# esp32_c6_a1_SoC.net
KiCad netlist of a schematic drawn in Altium Designer
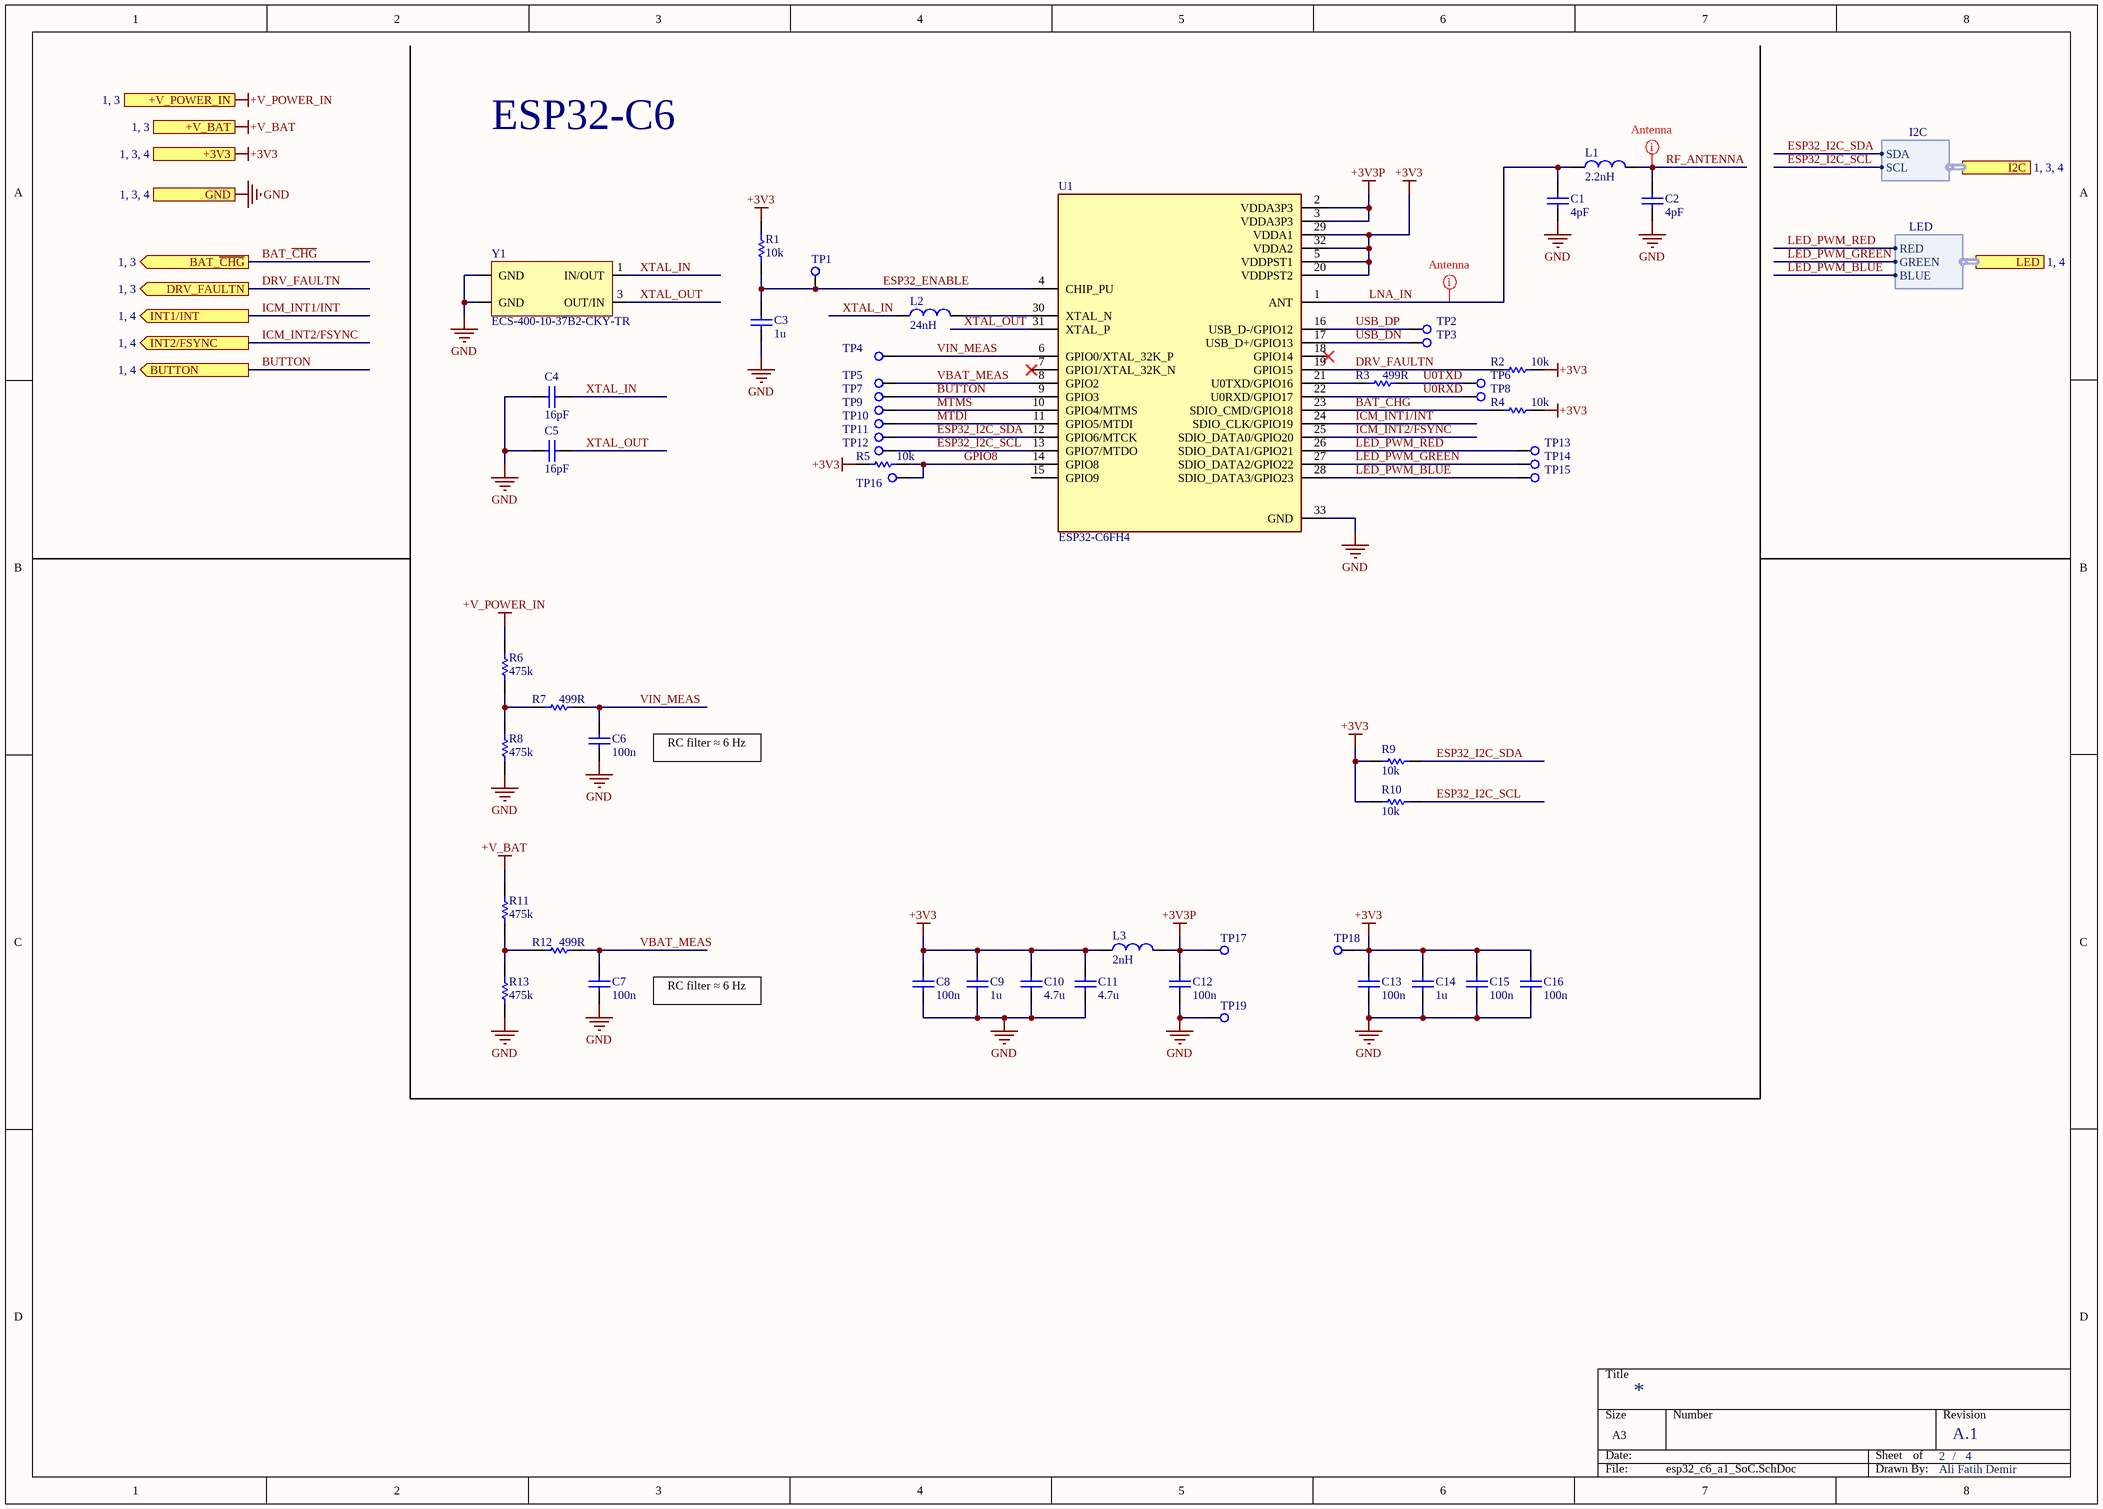
[diagram p0: esp32_c6_a1_SoC.SchDoc]

(export (version "E")
  (design (tool "Eeschema 10.0.6"))
  (components
    (comp (ref "C1")
      (value "4pF")
      (footprint "C_0201")
      (description "SMD 0201 Ceramic Chip Capacitor")
      (fields (field (name "MANUFACTURER") "Murata") (field (name "PART NUMBER") "?"))
      (libsource (lib "afd_lib") (part "C_0201"))
    )
    (comp (ref "C2")
      (value "4pF")
      (footprint "C_0201")
      (description "SMD 0201 Ceramic Chip Capacitor")
      (fields (field (name "MANUFACTURER") "Murata") (field (name "PART NUMBER") "?"))
      (libsource (lib "afd_lib") (part "C_0201"))
    )
    (comp (ref "C3")
      (value "1u")
      (footprint "C_0603")
      (description "SMD 0603 Ceramic Chip Capacitor")
      (fields (field (name "MANUFACTURER") "Samsung") (field (name "PART NUMBER") "?"))
      (libsource (lib "afd_lib") (part "C_0603"))
    )
    (comp (ref "C4")
      (value "16pF")
      (footprint "C_0402")
      (description "SMD 0402 Ceramic Chip Capacitor")
      (fields (field (name "MANUFACTURER") "Murata") (field (name "PART NUMBER") "?"))
      (libsource (lib "afd_lib") (part "C_0402"))
    )
    (comp (ref "C5")
      (value "16pF")
      (footprint "C_0402")
      (description "SMD 0402 Ceramic Chip Capacitor")
      (fields (field (name "MANUFACTURER") "Murata") (field (name "PART NUMBER") "?"))
      (libsource (lib "afd_lib") (part "C_0402"))
    )
    (comp (ref "C6")
      (value "100n")
      (footprint "C_0402")
      (description "SMD 0402 Ceramic Chip Capacitor")
      (fields (field (name "MANUFACTURER") "Samsung") (field (name "PART NUMBER") "?"))
      (libsource (lib "afd_lib") (part "C_0402"))
    )
    (comp (ref "C7")
      (value "100n")
      (footprint "C_0402")
      (description "SMD 0402 Ceramic Chip Capacitor")
      (fields (field (name "MANUFACTURER") "Samsung") (field (name "PART NUMBER") "?"))
      (libsource (lib "afd_lib") (part "C_0402"))
    )
    (comp (ref "C8")
      (value "100n")
      (footprint "C_0402")
      (description "SMD 0402 Ceramic Chip Capacitor")
      (fields (field (name "MANUFACTURER") "Samsung") (field (name "PART NUMBER") "?"))
      (libsource (lib "afd_lib") (part "C_0402"))
    )
    (comp (ref "C9")
      (value "1u")
      (footprint "C_0603")
      (description "SMD 0603 Ceramic Chip Capacitor")
      (fields (field (name "MANUFACTURER") "Samsung") (field (name "PART NUMBER") "?"))
      (libsource (lib "afd_lib") (part "C_0603"))
    )
    (comp (ref "C10")
      (value "4.7u")
      (footprint "C_0603")
      (description "SMD 0603 Ceramic Chip Capacitor")
      (fields (field (name "MANUFACTURER") "Samsung") (field (name "PART NUMBER") "?"))
      (libsource (lib "afd_lib") (part "C_0603"))
    )
    (comp (ref "C11")
      (value "4.7u")
      (footprint "C_0603")
      (description "SMD 0603 Ceramic Chip Capacitor")
      (fields (field (name "MANUFACTURER") "Samsung") (field (name "PART NUMBER") "?"))
      (libsource (lib "afd_lib") (part "C_0603"))
    )
    (comp (ref "C12")
      (value "100n")
      (footprint "C_0402")
      (description "SMD 0402 Ceramic Chip Capacitor")
      (fields (field (name "MANUFACTURER") "Samsung") (field (name "PART NUMBER") "?"))
      (libsource (lib "afd_lib") (part "C_0402"))
    )
    (comp (ref "C13")
      (value "100n")
      (footprint "C_0402")
      (description "SMD 0402 Ceramic Chip Capacitor")
      (fields (field (name "MANUFACTURER") "Samsung") (field (name "PART NUMBER") "?"))
      (libsource (lib "afd_lib") (part "C_0402"))
    )
    (comp (ref "C14")
      (value "1u")
      (footprint "C_0603")
      (description "SMD 0603 Ceramic Chip Capacitor")
      (fields (field (name "MANUFACTURER") "Samsung") (field (name "PART NUMBER") "?"))
      (libsource (lib "afd_lib") (part "C_0603"))
    )
    (comp (ref "C15")
      (value "100n")
      (footprint "C_0402")
      (description "SMD 0402 Ceramic Chip Capacitor")
      (fields (field (name "MANUFACTURER") "Samsung") (field (name "PART NUMBER") "?"))
      (libsource (lib "afd_lib") (part "C_0402"))
    )
    (comp (ref "C16")
      (value "100n")
      (footprint "C_0402")
      (description "SMD 0402 Ceramic Chip Capacitor")
      (fields (field (name "MANUFACTURER") "Samsung") (field (name "PART NUMBER") "?"))
      (libsource (lib "afd_lib") (part "C_0402"))
    )
    (comp (ref "L1")
      (value "2.2nH")
      (footprint "L_0201")
      (description "SMD 0201 Inductor")
      (fields (field (name "MANUFACTURER") "Murata") (field (name "PART NUMBER") "?"))
      (libsource (lib "afd_lib") (part "L_0201"))
    )
    (comp (ref "L2")
      (value "24nH")
      (footprint "L_0201")
      (description "SMD 0201 Inductor")
      (fields (field (name "MANUFACTURER") "Murata") (field (name "PART NUMBER") "?"))
      (libsource (lib "afd_lib") (part "L_0201"))
    )
    (comp (ref "L3")
      (value "2nH")
      (footprint "L_0402")
      (description "SMD 0402 Inductor")
      (fields (field (name "MANUFACTURER") "Murata") (field (name "PART NUMBER") "?"))
      (libsource (lib "afd_lib") (part "L_0402"))
    )
    (comp (ref "R1")
      (value "10k")
      (footprint "R_0402")
      (description "SMD 0402 Rectangular Thick Film Chip Resistor")
      (fields (field (name "MANUFACTURER") "Yageo") (field (name "PART NUMBER") "?"))
      (libsource (lib "afd_lib") (part "R_0402"))
    )
    (comp (ref "R2")
      (value "10k")
      (footprint "R_0402")
      (description "SMD 0402 Rectangular Thick Film Chip Resistor")
      (fields (field (name "MANUFACTURER") "Yageo") (field (name "PART NUMBER") "?"))
      (libsource (lib "afd_lib") (part "R_0402"))
    )
    (comp (ref "R3")
      (value "499R")
      (footprint "R_0402")
      (description "SMD 0402 Rectangular Thick Film Chip Resistor")
      (fields (field (name "MANUFACTURER") "Yageo") (field (name "PART NUMBER") "?"))
      (libsource (lib "afd_lib") (part "R_0402"))
    )
    (comp (ref "R4")
      (value "10k")
      (footprint "R_0402")
      (description "SMD 0402 Rectangular Thick Film Chip Resistor")
      (fields (field (name "MANUFACTURER") "Yageo") (field (name "PART NUMBER") "?"))
      (libsource (lib "afd_lib") (part "R_0402"))
    )
    (comp (ref "R5")
      (value "10k")
      (footprint "R_0402")
      (description "SMD 0402 Rectangular Thick Film Chip Resistor")
      (fields (field (name "MANUFACTURER") "Yageo") (field (name "PART NUMBER") "?"))
      (libsource (lib "afd_lib") (part "R_0402"))
    )
    (comp (ref "R6")
      (value "475k")
      (footprint "R_0402")
      (description "SMD 0402 Rectangular Thick Film Chip Resistor")
      (fields (field (name "MANUFACTURER") "Yageo") (field (name "PART NUMBER") "?"))
      (libsource (lib "afd_lib") (part "R_0402"))
    )
    (comp (ref "R7")
      (value "499R")
      (footprint "R_0402")
      (description "SMD 0402 Rectangular Thick Film Chip Resistor")
      (fields (field (name "MANUFACTURER") "Yageo") (field (name "PART NUMBER") "?"))
      (libsource (lib "afd_lib") (part "R_0402"))
    )
    (comp (ref "R8")
      (value "475k")
      (footprint "R_0402")
      (description "SMD 0402 Rectangular Thick Film Chip Resistor")
      (fields (field (name "MANUFACTURER") "Yageo") (field (name "PART NUMBER") "?"))
      (libsource (lib "afd_lib") (part "R_0402"))
    )
    (comp (ref "R9")
      (value "10k")
      (footprint "R_0402")
      (description "SMD 0402 Rectangular Thick Film Chip Resistor")
      (fields (field (name "MANUFACTURER") "Yageo") (field (name "PART NUMBER") "?"))
      (libsource (lib "afd_lib") (part "R_0402"))
    )
    (comp (ref "R10")
      (value "10k")
      (footprint "R_0402")
      (description "SMD 0402 Rectangular Thick Film Chip Resistor")
      (fields (field (name "MANUFACTURER") "Yageo") (field (name "PART NUMBER") "?"))
      (libsource (lib "afd_lib") (part "R_0402"))
    )
    (comp (ref "R11")
      (value "475k")
      (footprint "R_0402")
      (description "SMD 0402 Rectangular Thick Film Chip Resistor")
      (fields (field (name "MANUFACTURER") "Yageo") (field (name "PART NUMBER") "?"))
      (libsource (lib "afd_lib") (part "R_0402"))
    )
    (comp (ref "R12")
      (value "499R")
      (footprint "R_0402")
      (description "SMD 0402 Rectangular Thick Film Chip Resistor")
      (fields (field (name "MANUFACTURER") "Yageo") (field (name "PART NUMBER") "?"))
      (libsource (lib "afd_lib") (part "R_0402"))
    )
    (comp (ref "R13")
      (value "475k")
      (footprint "R_0402")
      (description "SMD 0402 Rectangular Thick Film Chip Resistor")
      (fields (field (name "MANUFACTURER") "Yageo") (field (name "PART NUMBER") "?"))
      (libsource (lib "afd_lib") (part "R_0402"))
    )
    (comp (ref "TP1")
      (value "TP")
      (footprint "tp_round_80")
      (description "Test Point")
      (libsource (lib "afd_lib") (part "TP"))
    )
    (comp (ref "TP2")
      (value "TP")
      (footprint "tp_round_80")
      (description "Test Point")
      (libsource (lib "afd_lib") (part "TP"))
    )
    (comp (ref "TP3")
      (value "TP")
      (footprint "tp_round_80")
      (description "Test Point")
      (libsource (lib "afd_lib") (part "TP"))
    )
    (comp (ref "TP4")
      (value "TP")
      (footprint "tp_round_80")
      (description "Test Point")
      (libsource (lib "afd_lib") (part "TP"))
    )
    (comp (ref "TP5")
      (value "TP")
      (footprint "tp_round_80")
      (description "Test Point")
      (libsource (lib "afd_lib") (part "TP"))
    )
    (comp (ref "TP6")
      (value "TP")
      (footprint "tp_round_80")
      (description "Test Point")
      (libsource (lib "afd_lib") (part "TP"))
    )
    (comp (ref "TP7")
      (value "TP")
      (footprint "tp_round_80")
      (description "Test Point")
      (libsource (lib "afd_lib") (part "TP"))
    )
    (comp (ref "TP8")
      (value "TP")
      (footprint "tp_round_80")
      (description "Test Point")
      (libsource (lib "afd_lib") (part "TP"))
    )
    (comp (ref "TP9")
      (value "TP")
      (footprint "tp_round_80")
      (description "Test Point")
      (libsource (lib "afd_lib") (part "TP"))
    )
    (comp (ref "TP10")
      (value "TP")
      (footprint "tp_round_80")
      (description "Test Point")
      (libsource (lib "afd_lib") (part "TP"))
    )
    (comp (ref "TP11")
      (value "TP")
      (footprint "tp_round_80")
      (description "Test Point")
      (libsource (lib "afd_lib") (part "TP"))
    )
    (comp (ref "TP12")
      (value "TP")
      (footprint "tp_round_80")
      (description "Test Point")
      (libsource (lib "afd_lib") (part "TP"))
    )
    (comp (ref "TP13")
      (value "TP")
      (footprint "tp_round_80")
      (description "Test Point")
      (libsource (lib "afd_lib") (part "TP"))
    )
    (comp (ref "TP14")
      (value "TP")
      (footprint "tp_round_80")
      (description "Test Point")
      (libsource (lib "afd_lib") (part "TP"))
    )
    (comp (ref "TP15")
      (value "TP")
      (footprint "tp_round_80")
      (description "Test Point")
      (libsource (lib "afd_lib") (part "TP"))
    )
    (comp (ref "TP16")
      (value "TP")
      (footprint "tp_round_80")
      (description "Test Point")
      (libsource (lib "afd_lib") (part "TP"))
    )
    (comp (ref "TP17")
      (value "TP")
      (footprint "tp_round_80")
      (description "Test Point")
      (libsource (lib "afd_lib") (part "TP"))
    )
    (comp (ref "TP18")
      (value "TP")
      (footprint "tp_round_80")
      (description "Test Point")
      (libsource (lib "afd_lib") (part "TP"))
    )
    (comp (ref "TP19")
      (value "TP")
      (footprint "tp_round_80")
      (description "Test Point")
      (libsource (lib "afd_lib") (part "TP"))
    )
    (comp (ref "U1")
      (value "ESP32-C6FH4")
      (footprint "QFN50P500X500X90-33N")
      (fields (field (name "MANUFACTURER") "Espressif Systems"))
      (libsource (lib "afd_lib") (part "ESP32-C6FH4"))
    )
    (comp (ref "Y1")
      (value "ECS-400-10-37B2-CKY-TR")
      (footprint "XTAL_ECS-400-10-37B2-CKY-TR")
      (description "40 MHz Â±10ppm Crystal 10pF 40 Ohms 4-SMD, No Lead")
      (fields
        (field (name "DIGI-KEY_PART_NUMBER") "50-ECS-400-10-37B2-CKY-TR-ND")
        (field (name "MANUFACTURER") "ECS Inc.")
      )
      (libsource (lib "afd_lib") (part "ECS-400-10-37B2-CKY-TR"))
    )
  )
  (nets
    (net (code "3") (name "+3V3") (class "Default")
      (node (ref "C10") (pin "2") (pinfunction "2_2") (pintype "passive"))
      (node (ref "C11") (pin "2") (pinfunction "2_2") (pintype "passive"))
      (node (ref "C13") (pin "2") (pinfunction "2_2") (pintype "passive"))
      (node (ref "C14") (pin "2") (pinfunction "2_2") (pintype "passive"))
      (node (ref "C15") (pin "2") (pinfunction "2_2") (pintype "passive"))
      (node (ref "C16") (pin "2") (pinfunction "2_2") (pintype "passive"))
      (node (ref "C8") (pin "2") (pinfunction "2_2") (pintype "passive"))
      (node (ref "C9") (pin "2") (pinfunction "2_2") (pintype "passive"))
      (node (ref "L3") (pin "1") (pinfunction "1_1") (pintype "passive"))
      (node (ref "R1") (pin "2") (pinfunction "2_2") (pintype "passive"))
      (node (ref "R10") (pin "2") (pinfunction "2_2") (pintype "passive"))
      (node (ref "R2") (pin "2") (pinfunction "2_2") (pintype "passive"))
      (node (ref "R4") (pin "2") (pinfunction "2_2") (pintype "passive"))
      (node (ref "R5") (pin "1") (pinfunction "1_1") (pintype "passive"))
      (node (ref "R9") (pin "2") (pinfunction "2_2") (pintype "passive"))
      (node (ref "TP18") (pin "1") (pinfunction "1_1") (pintype "passive"))
      (node (ref "U1") (pin "20") (pinfunction "VDDPST2_20") (pintype "passive"))
      (node (ref "U1") (pin "29") (pinfunction "VDDA1_29") (pintype "passive"))
      (node (ref "U1") (pin "32") (pinfunction "VDDA2_32") (pintype "passive"))
      (node (ref "U1") (pin "5") (pinfunction "VDDPST1_5") (pintype "passive"))
    )
    (net (code "4") (name "+3V3P") (class "Default")
      (node (ref "C12") (pin "2") (pinfunction "2_2") (pintype "passive"))
      (node (ref "L3") (pin "2") (pinfunction "2_2") (pintype "passive"))
      (node (ref "TP17") (pin "1") (pinfunction "1_1") (pintype "passive"))
      (node (ref "U1") (pin "2") (pinfunction "VDDA3P3_2") (pintype "passive"))
      (node (ref "U1") (pin "3") (pinfunction "VDDA3P3_3") (pintype "passive"))
    )
    (net (code "5") (name "+V_BAT") (class "Default")
      (node (ref "R11") (pin "2") (pinfunction "2_2") (pintype "passive"))
    )
    (net (code "6") (name "+V_POWER_IN") (class "Default")
      (node (ref "R6") (pin "2") (pinfunction "2_2") (pintype "passive"))
    )
    (net (code "7") (name "/BAT_~{CHG}") (class "Default")
      (node (ref "R4") (pin "1") (pinfunction "1_1") (pintype "passive"))
      (node (ref "U1") (pin "23") (pinfunction "SDIO_CMD/GPIO18_23") (pintype "passive"))
    )
    (net (code "8") (name "/BUTTON") (class "Default")
      (node (ref "TP7") (pin "1") (pinfunction "1_1") (pintype "passive"))
      (node (ref "U1") (pin "9") (pinfunction "GPIO3_9") (pintype "passive"))
    )
    (net (code "9") (name "/DRV_FAULTN") (class "Default")
      (node (ref "R2") (pin "1") (pinfunction "1_1") (pintype "passive"))
      (node (ref "U1") (pin "19") (pinfunction "GPIO15_19") (pintype "passive"))
    )
    (net (code "10") (name "/ESP32_ENABLE") (class "Default")
      (node (ref "C3") (pin "2") (pinfunction "2_2") (pintype "passive"))
      (node (ref "R1") (pin "1") (pinfunction "1_1") (pintype "passive"))
      (node (ref "TP1") (pin "1") (pinfunction "1_1") (pintype "passive"))
      (node (ref "U1") (pin "4") (pinfunction "CHIP_PU_4") (pintype "passive"))
    )
    (net (code "11") (name "/ESP32_I2C_SCL") (class "Default")
      (node (ref "R10") (pin "1") (pinfunction "1_1") (pintype "passive"))
      (node (ref "TP12") (pin "1") (pinfunction "1_1") (pintype "passive"))
      (node (ref "U1") (pin "13") (pinfunction "GPIO7/MTDO_13") (pintype "passive"))
    )
    (net (code "12") (name "/ESP32_I2C_SDA") (class "Default")
      (node (ref "R9") (pin "1") (pinfunction "1_1") (pintype "passive"))
      (node (ref "TP11") (pin "1") (pinfunction "1_1") (pintype "passive"))
      (node (ref "U1") (pin "12") (pinfunction "GPIO6/MTCK_12") (pintype "passive"))
    )
    (net (code "13") (name "/GPIO8") (class "Default")
      (node (ref "R5") (pin "2") (pinfunction "2_2") (pintype "passive"))
      (node (ref "TP16") (pin "1") (pinfunction "1_1") (pintype "passive"))
      (node (ref "U1") (pin "14") (pinfunction "GPIO8_14") (pintype "passive"))
    )
    (net (code "14") (name "/ICM_INT1{slash}INT") (class "Default")
      (node (ref "U1") (pin "24") (pinfunction "SDIO_CLK/GPIO19_24") (pintype "passive"))
    )
    (net (code "15") (name "/ICM_INT2{slash}FSYNC") (class "Default")
      (node (ref "U1") (pin "25") (pinfunction "SDIO_DATA0/GPIO20_25") (pintype "passive"))
    )
    (net (code "16") (name "/LED_PWM_BLUE") (class "Default")
      (node (ref "TP15") (pin "1") (pinfunction "1_1") (pintype "passive"))
      (node (ref "U1") (pin "28") (pinfunction "SDIO_DATA3/GPIO23_28") (pintype "passive"))
    )
    (net (code "17") (name "/LED_PWM_GREEN") (class "Default")
      (node (ref "TP14") (pin "1") (pinfunction "1_1") (pintype "passive"))
      (node (ref "U1") (pin "27") (pinfunction "SDIO_DATA2/GPIO22_27") (pintype "passive"))
    )
    (net (code "18") (name "/LED_PWM_RED") (class "Default")
      (node (ref "TP13") (pin "1") (pinfunction "1_1") (pintype "passive"))
      (node (ref "U1") (pin "26") (pinfunction "SDIO_DATA1/GPIO21_26") (pintype "passive"))
    )
    (net (code "19") (name "/LNA_IN") (class "Default")
      (node (ref "C1") (pin "2") (pinfunction "2_2") (pintype "passive"))
      (node (ref "L1") (pin "1") (pinfunction "1_1") (pintype "passive"))
      (node (ref "U1") (pin "1") (pinfunction "ANT_1") (pintype "passive"))
    )
    (net (code "20") (name "/MTDI") (class "Default")
      (node (ref "TP10") (pin "1") (pinfunction "1_1") (pintype "passive"))
      (node (ref "U1") (pin "11") (pinfunction "GPIO5/MTDI_11") (pintype "passive"))
    )
    (net (code "21") (name "/MTMS") (class "Default")
      (node (ref "TP9") (pin "1") (pinfunction "1_1") (pintype "passive"))
      (node (ref "U1") (pin "10") (pinfunction "GPIO4/MTMS_10") (pintype "passive"))
    )
    (net (code "22") (name "/RF_ANTENNA") (class "Default")
      (node (ref "C2") (pin "2") (pinfunction "2_2") (pintype "passive"))
      (node (ref "L1") (pin "2") (pinfunction "2_2") (pintype "passive"))
    )
    (net (code "23") (name "/U0RXD") (class "Default")
      (node (ref "TP8") (pin "1") (pinfunction "1_1") (pintype "passive"))
      (node (ref "U1") (pin "22") (pinfunction "U0RXD/GPIO17_22") (pintype "passive"))
    )
    (net (code "24") (name "/U0TXD") (class "Default")
      (node (ref "R3") (pin "2") (pinfunction "2_2") (pintype "passive"))
      (node (ref "TP6") (pin "1") (pinfunction "1_1") (pintype "passive"))
    )
    (net (code "25") (name "/USB_DN") (class "Default")
      (node (ref "TP3") (pin "1") (pinfunction "1_1") (pintype "passive"))
      (node (ref "U1") (pin "17") (pinfunction "USB_D+/GPIO13_17") (pintype "passive"))
    )
    (net (code "26") (name "/USB_DP") (class "Default")
      (node (ref "TP2") (pin "1") (pinfunction "1_1") (pintype "passive"))
      (node (ref "U1") (pin "16") (pinfunction "USB_D-/GPIO12_16") (pintype "passive"))
    )
    (net (code "27") (name "/VBAT_MEAS") (class "Default")
      (node (ref "C7") (pin "2") (pinfunction "2_2") (pintype "passive"))
      (node (ref "R12") (pin "2") (pinfunction "2_2") (pintype "passive"))
      (node (ref "TP5") (pin "1") (pinfunction "1_1") (pintype "passive"))
      (node (ref "U1") (pin "8") (pinfunction "GPIO2_8") (pintype "passive"))
    )
    (net (code "28") (name "/VIN_MEAS") (class "Default")
      (node (ref "C6") (pin "2") (pinfunction "2_2") (pintype "passive"))
      (node (ref "R7") (pin "2") (pinfunction "2_2") (pintype "passive"))
      (node (ref "TP4") (pin "1") (pinfunction "1_1") (pintype "passive"))
      (node (ref "U1") (pin "6") (pinfunction "GPIO0/XTAL_32K_P_6") (pintype "passive"))
    )
    (net (code "29") (name "/XTAL_IN") (class "Default")
      (node (ref "C4") (pin "1") (pinfunction "1_1") (pintype "passive"))
      (node (ref "L2") (pin "1") (pinfunction "1_1") (pintype "passive"))
      (node (ref "Y1") (pin "1") (pinfunction "IN/OUT_1") (pintype "passive"))
    )
    (net (code "30") (name "/XTAL_OUT") (class "Default")
      (node (ref "C5") (pin "1") (pinfunction "1_1") (pintype "passive"))
      (node (ref "U1") (pin "31") (pinfunction "XTAL_P_31") (pintype "passive"))
      (node (ref "Y1") (pin "3") (pinfunction "OUT/IN_3") (pintype "passive"))
    )
    (net (code "33") (name "GND") (class "Default")
      (node (ref "C1") (pin "1") (pinfunction "1_1") (pintype "passive"))
      (node (ref "C10") (pin "1") (pinfunction "1_1") (pintype "passive"))
      (node (ref "C11") (pin "1") (pinfunction "1_1") (pintype "passive"))
      (node (ref "C12") (pin "1") (pinfunction "1_1") (pintype "passive"))
      (node (ref "C13") (pin "1") (pinfunction "1_1") (pintype "passive"))
      (node (ref "C14") (pin "1") (pinfunction "1_1") (pintype "passive"))
      (node (ref "C15") (pin "1") (pinfunction "1_1") (pintype "passive"))
      (node (ref "C16") (pin "1") (pinfunction "1_1") (pintype "passive"))
      (node (ref "C2") (pin "1") (pinfunction "1_1") (pintype "passive"))
      (node (ref "C3") (pin "1") (pinfunction "1_1") (pintype "passive"))
      (node (ref "C4") (pin "2") (pinfunction "2_2") (pintype "passive"))
      (node (ref "C5") (pin "2") (pinfunction "2_2") (pintype "passive"))
      (node (ref "C6") (pin "1") (pinfunction "1_1") (pintype "passive"))
      (node (ref "C7") (pin "1") (pinfunction "1_1") (pintype "passive"))
      (node (ref "C8") (pin "1") (pinfunction "1_1") (pintype "passive"))
      (node (ref "C9") (pin "1") (pinfunction "1_1") (pintype "passive"))
      (node (ref "R13") (pin "1") (pinfunction "1_1") (pintype "passive"))
      (node (ref "R8") (pin "1") (pinfunction "1_1") (pintype "passive"))
      (node (ref "TP19") (pin "1") (pinfunction "1_1") (pintype "passive"))
      (node (ref "U1") (pin "33") (pinfunction "GND_33") (pintype "passive"))
      (node (ref "Y1") (pin "2") (pinfunction "GND_2") (pintype "power_in"))
      (node (ref "Y1") (pin "4") (pinfunction "GND_4") (pintype "power_in"))
    )
    (net (code "34") (name "Net-(R6-Pad1)") (class "Default")
      (node (ref "R6") (pin "1") (pinfunction "1_1") (pintype "passive"))
      (node (ref "R7") (pin "1") (pinfunction "1_1") (pintype "passive"))
      (node (ref "R8") (pin "2") (pinfunction "2_2") (pintype "passive"))
    )
    (net (code "35") (name "Net-(R11-Pad1)") (class "Default")
      (node (ref "R11") (pin "1") (pinfunction "1_1") (pintype "passive"))
      (node (ref "R12") (pin "1") (pinfunction "1_1") (pintype "passive"))
      (node (ref "R13") (pin "2") (pinfunction "2_2") (pintype "passive"))
    )
    (net (code "36") (name "Net-(U1-U0TXD{slash}GPIO16)") (class "Default")
      (node (ref "R3") (pin "1") (pinfunction "1_1") (pintype "passive"))
      (node (ref "U1") (pin "21") (pinfunction "U0TXD/GPIO16_21") (pintype "passive"))
    )
    (net (code "37") (name "Net-(U1-XTAL_N)") (class "Default")
      (node (ref "L2") (pin "2") (pinfunction "2_2") (pintype "passive"))
      (node (ref "U1") (pin "30") (pinfunction "XTAL_N_30") (pintype "passive"))
    )
    (net (code "38") (name "unconnected-(U1-GPIO1{slash}XTAL_32K_N-Pad7)") (class "Default")
      (node (ref "U1") (pin "7") (pinfunction "GPIO1/XTAL_32K_N_7") (pintype "passive+no_connect"))
    )
    (net (code "39") (name "unconnected-(U1-GPIO9-Pad15)") (class "Default")
      (node (ref "U1") (pin "15") (pinfunction "GPIO9_15") (pintype "passive"))
    )
    (net (code "40") (name "unconnected-(U1-GPIO14-Pad18)") (class "Default")
      (node (ref "U1") (pin "18") (pinfunction "GPIO14_18") (pintype "passive+no_connect"))
    )
  )
)
